# pca20020_sheet5_motion_sensors.net
KiCad netlist of a schematic drawn in Altium Designer
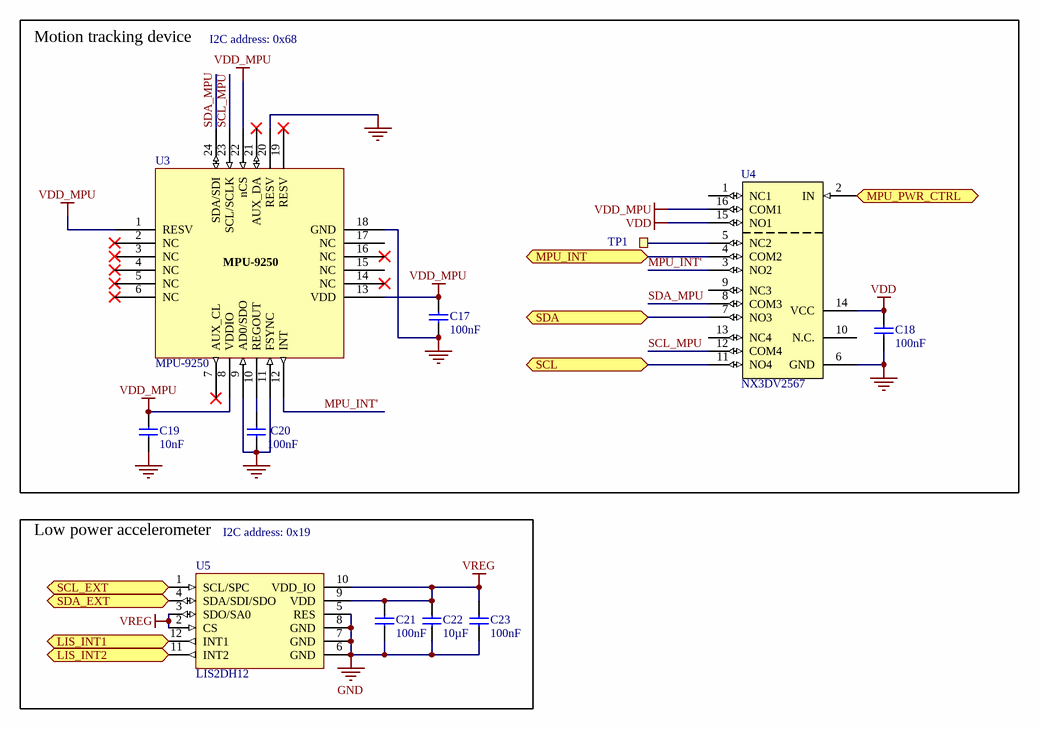
[diagram p0: pca20020_sheet5_motion_sensors.SchDoc]

(export (version "E")
  (design (tool "Eeschema 10.0.6"))
  (components
    (comp (ref "C17")
      (value "100nF")
      (footprint "CAPC1005X04L")
      (description "Capacitor, X7R, ±10%")
      (fields (field (name "PART NUMBER") "C0402-100n") (field (name "PUBLISHER") "Nordic Semiconductor"))
      (libsource (lib "Nordic Passive DB") (part "CAP"))
    )
    (comp (ref "C18")
      (value "100nF")
      (footprint "CAPC1005X04L")
      (description "Capacitor, X7R, ±10%")
      (fields (field (name "PART NUMBER") "C0402-100n") (field (name "PUBLISHER") "Nordic Semiconductor"))
      (libsource (lib "Nordic Passive DB") (part "CAP"))
    )
    (comp (ref "C19")
      (value "10nF")
      (footprint "CAPC1005X04L")
      (description "Capacitor, X7R, ±10%")
      (fields (field (name "PART NUMBER") "C0402-10n") (field (name "PUBLISHER") "Nordic Semiconductor"))
      (libsource (lib "Nordic Passive DB") (part "CAP"))
    )
    (comp (ref "C20")
      (value "100nF")
      (footprint "CAPC1005X04L")
      (description "Capacitor, X7R, ±10%")
      (fields (field (name "PART NUMBER") "C0402-100n") (field (name "PUBLISHER") "Nordic Semiconductor"))
      (libsource (lib "Nordic Passive DB") (part "CAP"))
    )
    (comp (ref "C21")
      (value "100nF")
      (footprint "CAPC1005X04L")
      (description "Capacitor, X7R, ±10%")
      (fields (field (name "PART NUMBER") "C0402-100n") (field (name "PUBLISHER") "Nordic Semiconductor"))
      (libsource (lib "Nordic Passive DB") (part "CAP"))
    )
    (comp (ref "C22")
      (value "10µF")
      (footprint "CAPC1608X06L")
      (description "Capacitor, X5R, ±20%")
      (fields (field (name "PART NUMBER") "C0603-10µ") (field (name "PUBLISHER") "Nordic Semiconductor"))
      (libsource (lib "Nordic Passive DB") (part "CAP"))
    )
    (comp (ref "C23")
      (value "100nF")
      (footprint "CAPC1005X04L")
      (description "Capacitor, X7R, ±10%")
      (fields (field (name "PART NUMBER") "C0402-100n") (field (name "PUBLISHER") "Nordic Semiconductor"))
      (libsource (lib "Nordic Passive DB") (part "CAP"))
    )
    (comp (ref "TP1")
      (value "TP")
      (footprint "TESTPAD-TH")
      (description "Testpoint, through hole")
      (fields (field (name "PART NUMBER") "Testpoint TH") (field (name "PUBLISHER") "Nordic Semiconductor"))
      (libsource (lib "Nordic Passive DB") (part "TESTPAD"))
    )
    (comp (ref "U3")
      (value "MPU-9250")
      (footprint "QFN40P300X300X105_HS-25N")
      (description "9-axis MotionTracking™ Device")
      (fields (field (name "MANUFACTURER") "InvenSense") (field (name "PUBLISHER") "Nordic Semiconductor"))
      (libsource (lib "Nordic Active DB") (part "MPU-9250"))
    )
    (comp (ref "U4")
      (value "NX3DV2567")
      (footprint "XQFN40P180X260X50-16N")
      (description "Low-ohmic four-pole double-throw analog switch")
      (fields
        (field (name "PART NUMBER") "NX3DV2567GU")
        (field (name "MANUFACTURER") "NXP Semiconductors")
        (field (name "PUBLISHER") "Nordic Semiconductor")
      )
      (libsource (lib "Nordic Active DB") (part "NX3DV2567"))
    )
    (comp (ref "U5")
      (value "LIS2DH12")
      (footprint "LGA50P200X200X100-12N")
      (description "3-axis - ±2g/±4g/±8g/±16g digital output femto accelerometer")
      (fields
        (field (name "MANUFACTURER") "STMicroelectronics")
        (field (name "PUBLISHER") "Nordic Semiconductor")
      )
      (libsource (lib "Nordic Active DB") (part "LIS2xx12"))
    )
  )
  (nets
    (net (code "1") (name "/LIS_INT1") (class "Default")
      (node (ref "U5") (pin "12") (pinfunction "INT1_12") (pintype "output"))
    )
    (net (code "2") (name "/LIS_INT2") (class "Default")
      (node (ref "U5") (pin "11") (pinfunction "INT2_11") (pintype "output"))
    )
    (net (code "3") (name "/MPU_INT") (class "Default")
      (node (ref "U4") (pin "4") (pinfunction "COM2_4") (pintype "bidirectional"))
    )
    (net (code "4") (name "/MPU_INT'") (class "Default")
      (node (ref "U3") (pin "12") (pinfunction "INT_12") (pintype "output"))
      (node (ref "U4") (pin "3") (pinfunction "NO2_3") (pintype "bidirectional"))
    )
    (net (code "5") (name "/MPU_PWR_CTRL") (class "Default")
      (node (ref "U4") (pin "2") (pinfunction "IN_2") (pintype "input"))
    )
    (net (code "6") (name "/SCL") (class "Default")
      (node (ref "U4") (pin "11") (pinfunction "NO4_11") (pintype "bidirectional"))
    )
    (net (code "7") (name "/SCL_EXT") (class "Default")
      (node (ref "U5") (pin "1") (pinfunction "SCL/SPC_1") (pintype "input"))
    )
    (net (code "8") (name "/SCL_MPU") (class "Default")
      (node (ref "U3") (pin "23") (pinfunction "SCL/SCLK_23") (pintype "input"))
      (node (ref "U4") (pin "12") (pinfunction "COM4_12") (pintype "bidirectional"))
    )
    (net (code "9") (name "/SDA") (class "Default")
      (node (ref "U4") (pin "7") (pinfunction "NO3_7") (pintype "bidirectional"))
    )
    (net (code "10") (name "/SDA_EXT") (class "Default")
      (node (ref "U5") (pin "4") (pinfunction "SDA/SDI/SDO_4") (pintype "bidirectional"))
    )
    (net (code "11") (name "/SDA_MPU") (class "Default")
      (node (ref "U3") (pin "24") (pinfunction "SDA/SDI_24") (pintype "bidirectional"))
      (node (ref "U4") (pin "8") (pinfunction "COM3_8") (pintype "bidirectional"))
    )
    (net (code "12") (name "GND") (class "Default")
      (node (ref "C17") (pin "1") (pinfunction "1_1") (pintype "passive"))
      (node (ref "C18") (pin "1") (pinfunction "1_1") (pintype "passive"))
      (node (ref "C19") (pin "1") (pinfunction "1_1") (pintype "passive"))
      (node (ref "C20") (pin "1") (pinfunction "1_1") (pintype "passive"))
      (node (ref "C21") (pin "1") (pinfunction "1_1") (pintype "passive"))
      (node (ref "C22") (pin "1") (pinfunction "1_1") (pintype "passive"))
      (node (ref "C23") (pin "1") (pinfunction "1_1") (pintype "passive"))
      (node (ref "U3") (pin "11") (pinfunction "FSYNC_11") (pintype "input"))
      (node (ref "U3") (pin "18") (pinfunction "GND_18") (pintype "power_in"))
      (node (ref "U3") (pin "20") (pinfunction "RESV_20") (pintype "passive"))
      (node (ref "U3") (pin "9") (pinfunction "AD0/SDO_9") (pintype "input"))
      (node (ref "U4") (pin "6") (pinfunction "GND_6") (pintype "power_in"))
      (node (ref "U5") (pin "5") (pinfunction "RES_5") (pintype "passive"))
      (node (ref "U5") (pin "6") (pinfunction "GND_6") (pintype "power_in"))
      (node (ref "U5") (pin "7") (pinfunction "GND_7") (pintype "power_in"))
      (node (ref "U5") (pin "8") (pinfunction "GND_8") (pintype "power_in"))
    )
    (net (code "13") (name "Net-(U3-REGOUT)") (class "Default")
      (node (ref "C20") (pin "2") (pinfunction "2_2") (pintype "passive"))
      (node (ref "U3") (pin "10") (pinfunction "REGOUT_10") (pintype "passive"))
    )
    (net (code "14") (name "Net-(U4-NC2)") (class "Default")
      (node (ref "TP1") (pin "1") (pinfunction "1_1") (pintype "passive"))
      (node (ref "U4") (pin "5") (pinfunction "NC2_5") (pintype "bidirectional"))
    )
    (net (code "15") (name "VDD") (class "Default")
      (node (ref "C18") (pin "2") (pinfunction "2_2") (pintype "passive"))
      (node (ref "U4") (pin "14") (pinfunction "VCC_14") (pintype "power_in"))
      (node (ref "U4") (pin "15") (pinfunction "NO1_15") (pintype "bidirectional"))
    )
    (net (code "16") (name "VDD_MPU") (class "Default")
      (node (ref "C17") (pin "2") (pinfunction "2_2") (pintype "passive"))
      (node (ref "C19") (pin "2") (pinfunction "2_2") (pintype "passive"))
      (node (ref "U3") (pin "1") (pinfunction "RESV_1") (pintype "passive"))
      (node (ref "U3") (pin "13") (pinfunction "VDD_13") (pintype "power_in"))
      (node (ref "U3") (pin "22") (pinfunction "nCS_22") (pintype "input"))
      (node (ref "U3") (pin "8") (pinfunction "VDDIO_8") (pintype "power_in"))
      (node (ref "U4") (pin "16") (pinfunction "COM1_16") (pintype "bidirectional"))
    )
    (net (code "17") (name "VREG") (class "Default")
      (node (ref "C21") (pin "2") (pinfunction "2_2") (pintype "passive"))
      (node (ref "C22") (pin "2") (pinfunction "2_2") (pintype "passive"))
      (node (ref "C23") (pin "2") (pinfunction "2_2") (pintype "passive"))
      (node (ref "U5") (pin "10") (pinfunction "VDD_IO_10") (pintype "power_in"))
      (node (ref "U5") (pin "2") (pinfunction "CS_2") (pintype "input"))
      (node (ref "U5") (pin "3") (pinfunction "SDO/SA0_3") (pintype "bidirectional"))
      (node (ref "U5") (pin "9") (pinfunction "VDD_9") (pintype "power_in"))
    )
    (net (code "18") (name "unconnected-(U3-AUX_CL-Pad7)") (class "Default")
      (node (ref "U3") (pin "7") (pinfunction "AUX_CL_7") (pintype "output+no_connect"))
    )
    (net (code "19") (name "unconnected-(U3-AUX_DA-Pad21)") (class "Default")
      (node (ref "U3") (pin "21") (pinfunction "AUX_DA_21") (pintype "bidirectional+no_connect"))
    )
    (net (code "20") (name "unconnected-(U3-NC-Pad2)") (class "Default")
      (node (ref "U3") (pin "2") (pinfunction "NC_2") (pintype "passive+no_connect"))
    )
    (net (code "21") (name "unconnected-(U3-NC-Pad3)") (class "Default")
      (node (ref "U3") (pin "3") (pinfunction "NC_3") (pintype "passive+no_connect"))
    )
    (net (code "22") (name "unconnected-(U3-NC-Pad4)") (class "Default")
      (node (ref "U3") (pin "4") (pinfunction "NC_4") (pintype "passive+no_connect"))
    )
    (net (code "23") (name "unconnected-(U3-NC-Pad5)") (class "Default")
      (node (ref "U3") (pin "5") (pinfunction "NC_5") (pintype "passive+no_connect"))
    )
    (net (code "24") (name "unconnected-(U3-NC-Pad6)") (class "Default")
      (node (ref "U3") (pin "6") (pinfunction "NC_6") (pintype "passive+no_connect"))
    )
    (net (code "25") (name "unconnected-(U3-NC-Pad14)") (class "Default")
      (node (ref "U3") (pin "14") (pinfunction "NC_14") (pintype "passive+no_connect"))
    )
    (net (code "26") (name "unconnected-(U3-NC-Pad15)") (class "Default")
      (node (ref "U3") (pin "15") (pinfunction "NC_15") (pintype "passive"))
    )
    (net (code "27") (name "unconnected-(U3-NC-Pad16)") (class "Default")
      (node (ref "U3") (pin "16") (pinfunction "NC_16") (pintype "passive+no_connect"))
    )
    (net (code "28") (name "unconnected-(U3-NC-Pad17)") (class "Default")
      (node (ref "U3") (pin "17") (pinfunction "NC_17") (pintype "passive"))
    )
    (net (code "29") (name "unconnected-(U3-RESV-Pad19)") (class "Default")
      (node (ref "U3") (pin "19") (pinfunction "RESV_19") (pintype "passive+no_connect"))
    )
    (net (code "30") (name "unconnected-(U4-N.C.-Pad10)") (class "Default")
      (node (ref "U4") (pin "10") (pinfunction "N.C._10") (pintype "passive"))
    )
    (net (code "31") (name "unconnected-(U4-NC1-Pad1)") (class "Default")
      (node (ref "U4") (pin "1") (pinfunction "NC1_1") (pintype "bidirectional"))
    )
    (net (code "32") (name "unconnected-(U4-NC3-Pad9)") (class "Default")
      (node (ref "U4") (pin "9") (pinfunction "NC3_9") (pintype "bidirectional"))
    )
    (net (code "33") (name "unconnected-(U4-NC4-Pad13)") (class "Default")
      (node (ref "U4") (pin "13") (pinfunction "NC4_13") (pintype "bidirectional"))
    )
  )
)
